# USB2BT2.net
KiCad netlist of a schematic drawn in Altium Designer
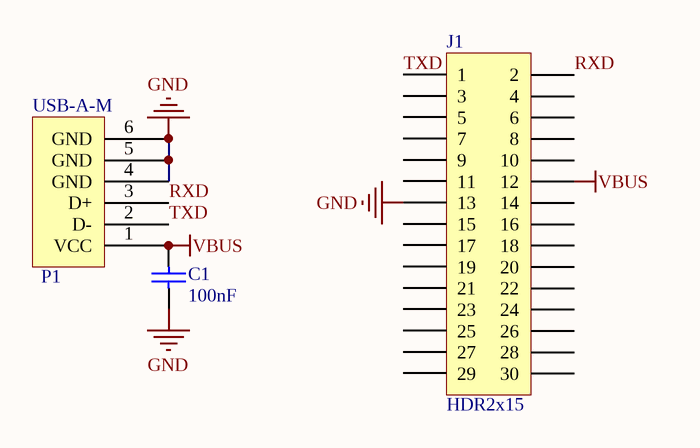
[diagram p0: USB2BT2.SchDoc]

(export (version "E")
  (design (tool "Eeschema 10.0.6"))
  (components
    (comp (ref "C1")
      (value "100nF")
      (footprint "0603C")
      (description "Capacitor")
      (fields (field (name "PUBLISHER") "Altium Limited"))
      (libsource (lib "Crazy_PCB") (part "Cap"))
    )
    (comp (ref "J1")
      (value "HDR2x15")
      (footprint "HC-05/06/08V15")
      (description "Connector")
      (libsource (lib "General") (part "HDR2x15"))
    )
    (comp (ref "P1") (value "USB-A-M") (footprint "USB-A-M") (libsource (lib "DX") (part "USB-B")))
  )
  (nets
    (net (code "1") (name "/RXD") (class "Default")
      (node (ref "J1") (pin "2") (pinfunction "2_2") (pintype "passive"))
      (node (ref "P1") (pin "3") (pinfunction "D+_3") (pintype "passive"))
    )
    (net (code "2") (name "/TXD") (class "Default")
      (node (ref "J1") (pin "1") (pinfunction "1_1") (pintype "passive"))
      (node (ref "P1") (pin "2") (pinfunction "D-_2") (pintype "passive"))
    )
    (net (code "3") (name "GND") (class "Default")
      (node (ref "C1") (pin "1") (pinfunction "1_1") (pintype "passive"))
      (node (ref "J1") (pin "13") (pinfunction "13_13") (pintype "passive"))
      (node (ref "P1") (pin "4") (pinfunction "GND_4") (pintype "passive"))
      (node (ref "P1") (pin "5") (pinfunction "GND_5") (pintype "passive"))
      (node (ref "P1") (pin "6") (pinfunction "GND_6") (pintype "passive"))
    )
    (net (code "4") (name "VBUS") (class "Default")
      (node (ref "C1") (pin "2") (pinfunction "2_2") (pintype "passive"))
      (node (ref "J1") (pin "12") (pinfunction "12_12") (pintype "passive"))
      (node (ref "P1") (pin "1") (pinfunction "VCC_1") (pintype "passive"))
    )
    (net (code "5") (name "unconnected-(J1-Pad3)") (class "Default")
      (node (ref "J1") (pin "3") (pinfunction "3_3") (pintype "passive"))
    )
    (net (code "6") (name "unconnected-(J1-Pad4)") (class "Default")
      (node (ref "J1") (pin "4") (pinfunction "4_4") (pintype "passive"))
    )
    (net (code "7") (name "unconnected-(J1-Pad5)") (class "Default")
      (node (ref "J1") (pin "5") (pinfunction "5_5") (pintype "passive"))
    )
    (net (code "8") (name "unconnected-(J1-Pad6)") (class "Default")
      (node (ref "J1") (pin "6") (pinfunction "6_6") (pintype "passive"))
    )
    (net (code "9") (name "unconnected-(J1-Pad7)") (class "Default")
      (node (ref "J1") (pin "7") (pinfunction "7_7") (pintype "passive"))
    )
    (net (code "10") (name "unconnected-(J1-Pad8)") (class "Default")
      (node (ref "J1") (pin "8") (pinfunction "8_8") (pintype "passive"))
    )
    (net (code "11") (name "unconnected-(J1-Pad9)") (class "Default")
      (node (ref "J1") (pin "9") (pinfunction "9_9") (pintype "passive"))
    )
    (net (code "12") (name "unconnected-(J1-Pad10)") (class "Default")
      (node (ref "J1") (pin "10") (pinfunction "10_10") (pintype "passive"))
    )
    (net (code "13") (name "unconnected-(J1-Pad11)") (class "Default")
      (node (ref "J1") (pin "11") (pinfunction "11_11") (pintype "passive"))
    )
    (net (code "14") (name "unconnected-(J1-Pad14)") (class "Default")
      (node (ref "J1") (pin "14") (pinfunction "14_14") (pintype "passive"))
    )
    (net (code "15") (name "unconnected-(J1-Pad15)") (class "Default")
      (node (ref "J1") (pin "15") (pinfunction "15_15") (pintype "passive"))
    )
    (net (code "16") (name "unconnected-(J1-Pad16)") (class "Default")
      (node (ref "J1") (pin "16") (pinfunction "16_16") (pintype "passive"))
    )
    (net (code "17") (name "unconnected-(J1-Pad17)") (class "Default")
      (node (ref "J1") (pin "17") (pinfunction "17_17") (pintype "passive"))
    )
    (net (code "18") (name "unconnected-(J1-Pad18)") (class "Default")
      (node (ref "J1") (pin "18") (pinfunction "18_18") (pintype "passive"))
    )
    (net (code "19") (name "unconnected-(J1-Pad19)") (class "Default")
      (node (ref "J1") (pin "19") (pinfunction "19_19") (pintype "passive"))
    )
    (net (code "20") (name "unconnected-(J1-Pad20)") (class "Default")
      (node (ref "J1") (pin "20") (pinfunction "20_20") (pintype "passive"))
    )
    (net (code "21") (name "unconnected-(J1-Pad21)") (class "Default")
      (node (ref "J1") (pin "21") (pinfunction "21_21") (pintype "passive"))
    )
    (net (code "22") (name "unconnected-(J1-Pad22)") (class "Default")
      (node (ref "J1") (pin "22") (pinfunction "22_22") (pintype "passive"))
    )
    (net (code "23") (name "unconnected-(J1-Pad23)") (class "Default")
      (node (ref "J1") (pin "23") (pinfunction "23_23") (pintype "passive"))
    )
    (net (code "24") (name "unconnected-(J1-Pad24)") (class "Default")
      (node (ref "J1") (pin "24") (pinfunction "24_24") (pintype "passive"))
    )
    (net (code "25") (name "unconnected-(J1-Pad25)") (class "Default")
      (node (ref "J1") (pin "25") (pinfunction "25_25") (pintype "passive"))
    )
    (net (code "26") (name "unconnected-(J1-Pad26)") (class "Default")
      (node (ref "J1") (pin "26") (pinfunction "26_26") (pintype "passive"))
    )
    (net (code "27") (name "unconnected-(J1-Pad27)") (class "Default")
      (node (ref "J1") (pin "27") (pinfunction "27_27") (pintype "passive"))
    )
    (net (code "28") (name "unconnected-(J1-Pad28)") (class "Default")
      (node (ref "J1") (pin "28") (pinfunction "28_28") (pintype "passive"))
    )
    (net (code "29") (name "unconnected-(J1-Pad29)") (class "Default")
      (node (ref "J1") (pin "29") (pinfunction "29_29") (pintype "passive"))
    )
    (net (code "30") (name "unconnected-(J1-Pad30)") (class "Default")
      (node (ref "J1") (pin "30") (pinfunction "30_30") (pintype "passive"))
    )
  )
)
